# R6DroneElectronics.net
KiCad netlist of a schematic drawn in EAGLE
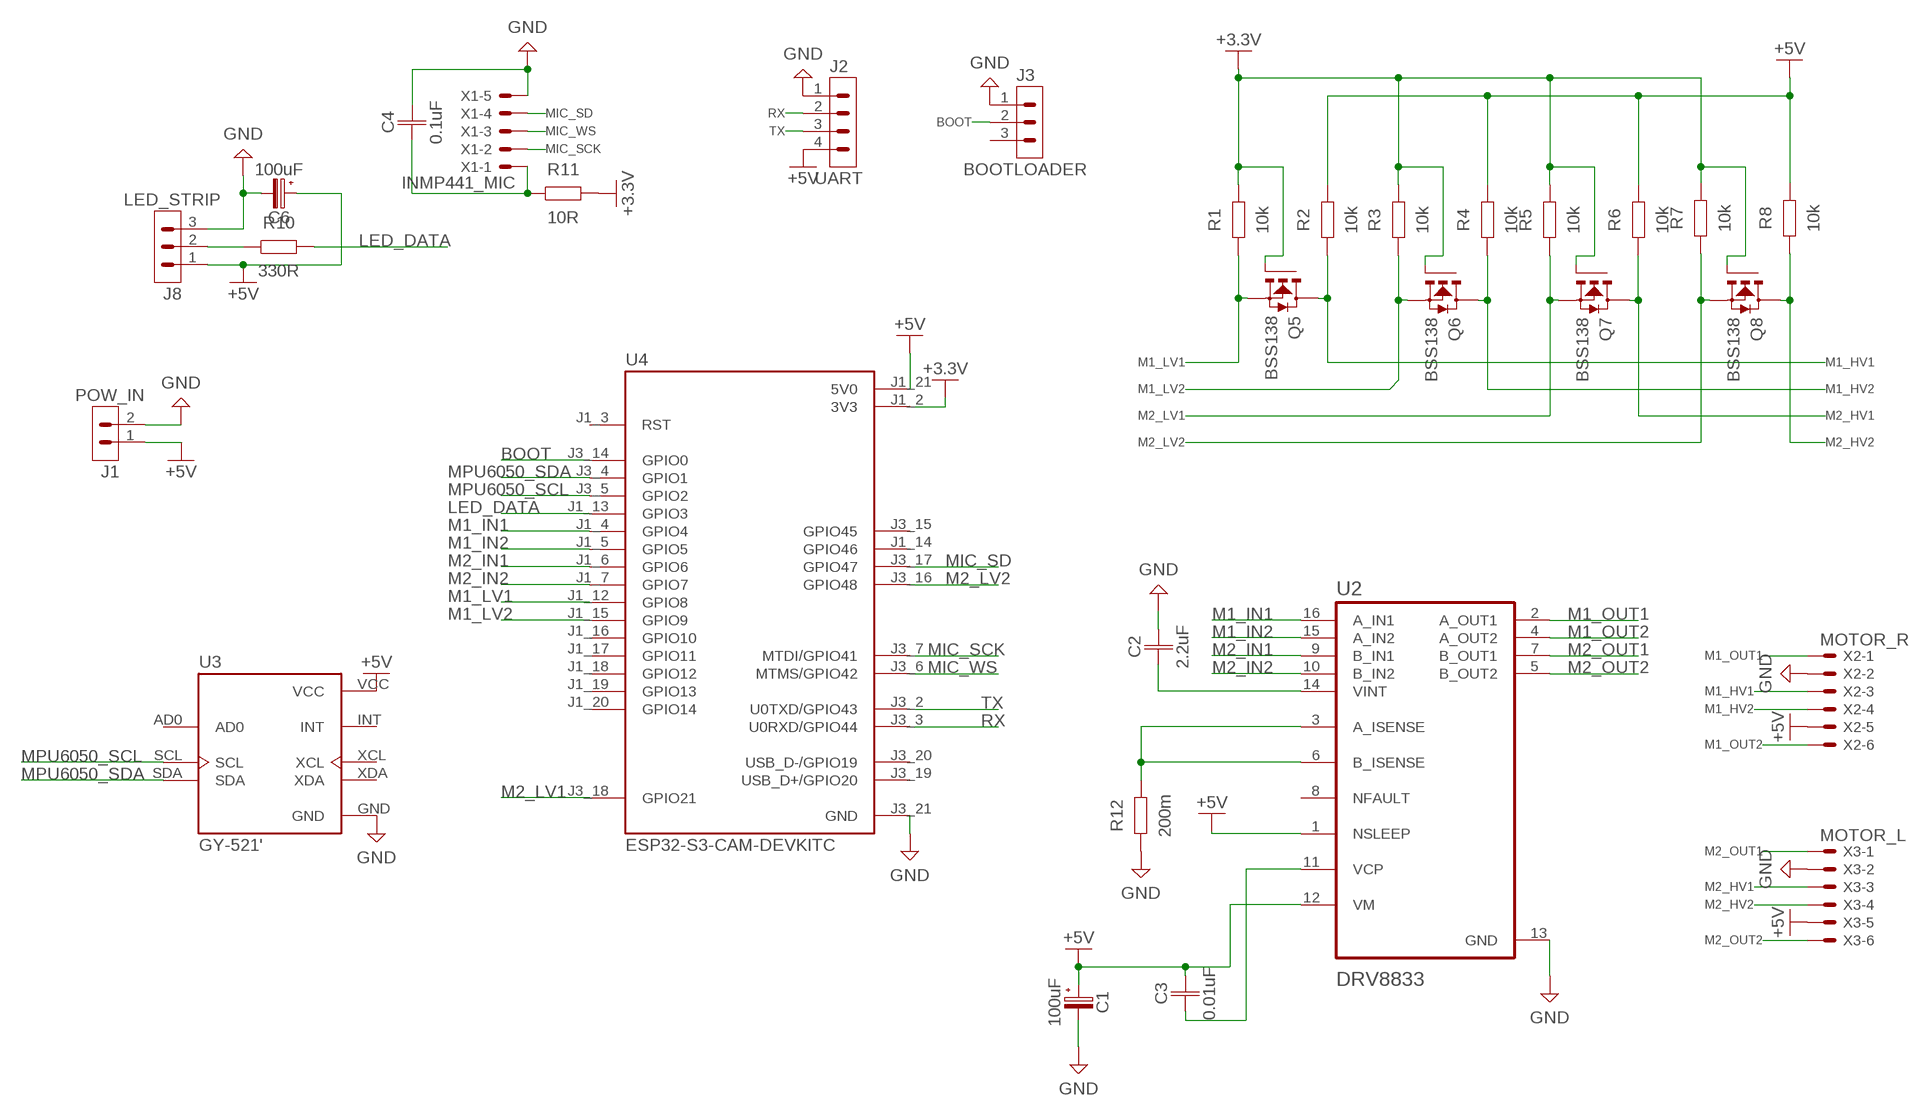
[diagram p0: schematic, sheet 1]

(export (version "E")
  (design (tool "Eeschema 10.0.6"))
  (components
    (comp (ref "C1")
      (value "100uF")
      (footprint "eagle-import:CAPAE1030X1050N")
      (libsource (lib "eagle-import") (part "C-POLECAP-10.5MM_"))
    )
    (comp (ref "C2")
      (value "2.2uF")
      (footprint "eagle-import:CAPC4532X135")
      (libsource (lib "eagle-import") (part "CCHIP-1812(4532-METRIC)_"))
    )
    (comp (ref "C3")
      (value "0.01uF")
      (footprint "eagle-import:CAPC4532X135")
      (libsource (lib "eagle-import") (part "CCHIP-1812(4532-METRIC)_"))
    )
    (comp (ref "C4")
      (value "0.1uF")
      (footprint "eagle-import:CAPC4532X135")
      (libsource (lib "eagle-import") (part "CCHIP-1812(4532-METRIC)_"))
    )
    (comp (ref "C6")
      (value "100uF")
      (footprint "eagle-import:CAPAE1030X1050N")
      (libsource (lib "eagle-import") (part "C-POLECAP-10.5MM_"))
    )
    (comp (ref "J1")
      (value "POW_IN")
      (footprint "eagle-import:B2B-XH-A")
      (fields (field (name "MANUFACTURER") "JST Sales America Inc.") (field (name "MPN") "B2B-XH-A"))
      (libsource (lib "eagle-import") (part "B2B-XH-A"))
    )
    (comp (ref "J2")
      (value "UART")
      (footprint "eagle-import:B4B-XH-A")
      (fields (field (name "MANUFACTURER") "JST Sales America Inc.") (field (name "MPN") "B4B-XH-A"))
      (libsource (lib "eagle-import") (part "B4B-XH-A"))
    )
    (comp (ref "J3")
      (value "BOOTLOADER")
      (footprint "eagle-import:B3B-XH-A")
      (fields (field (name "MANUFACTURER") "JST Sales America Inc.") (field (name "MPN") "B3B-XH-A"))
      (libsource (lib "eagle-import") (part "B3B-XH-A"))
    )
    (comp (ref "J8")
      (value "LED_STRIP")
      (footprint "eagle-import:B3B-XH-A")
      (fields (field (name "MANUFACTURER") "JST Sales America Inc.") (field (name "MPN") "B3B-XH-A"))
      (libsource (lib "eagle-import") (part "B3B-XH-A"))
    )
    (comp (ref "Q5")
      (value "BSS138")
      (footprint "eagle-import:SOT23")
      (fields (field (name "MANUFACTURER") "onsemi") (field (name "MPN") "BSS123L"))
      (libsource (lib "eagle-import") (part "NMOSFET__SOT23-GSDBSS123"))
    )
    (comp (ref "Q6")
      (value "BSS138")
      (footprint "eagle-import:SOT23")
      (fields (field (name "MANUFACTURER") "onsemi") (field (name "MPN") "BSS123L"))
      (libsource (lib "eagle-import") (part "NMOSFET__SOT23-GSDBSS123"))
    )
    (comp (ref "Q7")
      (value "BSS138")
      (footprint "eagle-import:SOT23")
      (fields (field (name "MANUFACTURER") "onsemi") (field (name "MPN") "BSS123L"))
      (libsource (lib "eagle-import") (part "NMOSFET__SOT23-GSDBSS123"))
    )
    (comp (ref "Q8")
      (value "BSS138")
      (footprint "eagle-import:SOT23")
      (fields (field (name "MANUFACTURER") "onsemi") (field (name "MPN") "BSS123L"))
      (libsource (lib "eagle-import") (part "NMOSFET__SOT23-GSDBSS123"))
    )
    (comp (ref "R1")
      (value "10k")
      (footprint "eagle-import:RESC3224X71")
      (libsource (lib "eagle-import") (part "RCHIP-1210(3225-METRIC)_"))
    )
    (comp (ref "R2")
      (value "10k")
      (footprint "eagle-import:RESC3224X71")
      (libsource (lib "eagle-import") (part "RCHIP-1210(3225-METRIC)_"))
    )
    (comp (ref "R3")
      (value "10k")
      (footprint "eagle-import:RESC3224X71")
      (libsource (lib "eagle-import") (part "RCHIP-1210(3225-METRIC)_"))
    )
    (comp (ref "R4")
      (value "10k")
      (footprint "eagle-import:RESC3224X71")
      (libsource (lib "eagle-import") (part "RCHIP-1210(3225-METRIC)_"))
    )
    (comp (ref "R5")
      (value "10k")
      (footprint "eagle-import:RESC3224X71")
      (libsource (lib "eagle-import") (part "RCHIP-1210(3225-METRIC)_"))
    )
    (comp (ref "R6")
      (value "10k")
      (footprint "eagle-import:RESC3224X71")
      (libsource (lib "eagle-import") (part "RCHIP-1210(3225-METRIC)_"))
    )
    (comp (ref "R7")
      (value "10k")
      (footprint "eagle-import:RESC3224X71")
      (libsource (lib "eagle-import") (part "RCHIP-1210(3225-METRIC)_"))
    )
    (comp (ref "R8")
      (value "10k")
      (footprint "eagle-import:RESC3224X71")
      (libsource (lib "eagle-import") (part "RCHIP-1210(3225-METRIC)_"))
    )
    (comp (ref "R10")
      (value "330R")
      (footprint "eagle-import:RESC3224X71")
      (libsource (lib "eagle-import") (part "RCHIP-1210(3225-METRIC)_"))
    )
    (comp (ref "R11")
      (value "10R")
      (footprint "eagle-import:RESC3224X71")
      (libsource (lib "eagle-import") (part "RCHIP-1210(3225-METRIC)_"))
    )
    (comp (ref "R12")
      (value "200m")
      (footprint "eagle-import:RESC3224X71")
      (libsource (lib "eagle-import") (part "RCHIP-1210(3225-METRIC)_"))
    )
    (comp (ref "U2")
      (value "DRV8833")
      (footprint "eagle-import:SOP65P640X120-16N")
      (fields
        (field (name "DIGIKEY_PART_NUMBER") "DRV8833PW-ND")
        (field (name "MF") "Texas Instruments")
        (field (name "MP") "DRV8833PW")
      )
      (libsource (lib "eagle-import") (part "DRV8833PW"))
    )
    (comp (ref "U3")
      (value "GY-521'")
      (footprint "eagle-import:MODULE_GY-521")
      (fields (field (name "MF") "GODREAM FORDREAM CO., LIMITED") (field (name "MP") "GY-521"))
      (libsource (lib "eagle-import") (part "GY-521'"))
    )
    (comp (ref "U4")
      (value "ESP32-S3-CAM-DEVKITC")
      (footprint "eagle-import:ESP32-S3-CAM-DEVKITC")
      (fields (field (name "MF") "Espressif Systems") (field (name "MP") "ESP32-S3-DEVKITC-1-N8R2"))
      (libsource (lib "eagle-import") (part "ESP32-S3-CAM-DEVKITC"))
    )
    (comp (ref "X1")
      (value "INMP441_MIC")
      (footprint "eagle-import:JST-XH-05-PACKAGE-LONG-PAD")
      (libsource (lib "eagle-import") (part "JST-XH-05-PIN-LONG-PAD"))
    )
    (comp (ref "X2")
      (value "MOTOR_R")
      (footprint "eagle-import:JST-XH-06-PACKAGE-LONG-PAD")
      (libsource (lib "eagle-import") (part "JST-XH-06-PIN-LONG-PAD"))
    )
    (comp (ref "X3")
      (value "MOTOR_L")
      (footprint "eagle-import:JST-XH-06-PACKAGE-LONG-PAD")
      (libsource (lib "eagle-import") (part "JST-XH-06-PIN-LONG-PAD"))
    )
  )
  (nets
    (net (code "1") (name "+3.3V") (class "Default")
      (node (ref "Q5") (pin "1") (pinfunction "G_1") (pintype "passive"))
      (node (ref "Q6") (pin "1") (pinfunction "G_1") (pintype "passive"))
      (node (ref "Q7") (pin "1") (pinfunction "G_1") (pintype "passive"))
      (node (ref "Q8") (pin "1") (pinfunction "G_1") (pintype "passive"))
      (node (ref "R1") (pin "2") (pinfunction "2_2") (pintype "passive"))
      (node (ref "R11") (pin "2") (pinfunction "2_2") (pintype "passive"))
      (node (ref "R3") (pin "2") (pinfunction "2_2") (pintype "passive"))
      (node (ref "R5") (pin "2") (pinfunction "2_2") (pintype "passive"))
      (node (ref "R7") (pin "2") (pinfunction "2_2") (pintype "passive"))
      (node (ref "U4") (pin "J1_2") (pinfunction "3V3_J1_2") (pintype "power_in"))
    )
    (net (code "2") (name "+5V") (class "Default")
      (node (ref "C1") (pin "1") (pinfunction "+_1") (pintype "passive"))
      (node (ref "C3") (pin "2") (pinfunction "2_2") (pintype "passive"))
      (node (ref "C6") (pin "1") (pinfunction "+_1") (pintype "passive"))
      (node (ref "J1") (pin "1") (pinfunction "1_1") (pintype "passive"))
      (node (ref "J2") (pin "4") (pinfunction "4_4") (pintype "passive"))
      (node (ref "J8") (pin "1") (pinfunction "1_1") (pintype "passive"))
      (node (ref "R2") (pin "2") (pinfunction "2_2") (pintype "passive"))
      (node (ref "R4") (pin "2") (pinfunction "2_2") (pintype "passive"))
      (node (ref "R6") (pin "2") (pinfunction "2_2") (pintype "passive"))
      (node (ref "R8") (pin "2") (pinfunction "2_2") (pintype "passive"))
      (node (ref "U2") (pin "1") (pinfunction "NSLEEP_1") (pintype "bidirectional"))
      (node (ref "U2") (pin "12") (pinfunction "VM_12") (pintype "bidirectional"))
      (node (ref "U3") (pin "VCC") (pinfunction "VCC_VCC") (pintype "power_in"))
      (node (ref "U4") (pin "J1_21") (pinfunction "5V0_J1_21") (pintype "power_in"))
      (node (ref "X2") (pin "5") (pinfunction "S_5") (pintype "passive"))
      (node (ref "X3") (pin "5") (pinfunction "S_5") (pintype "passive"))
    )
    (net (code "3") (name "/BOOT") (class "Default")
      (node (ref "J3") (pin "2") (pinfunction "2_2") (pintype "passive"))
      (node (ref "U4") (pin "J3_14") (pinfunction "GPIO0_J3_14") (pintype "bidirectional"))
    )
    (net (code "4") (name "/LED_DATA") (class "Default")
      (node (ref "R10") (pin "2") (pinfunction "2_2") (pintype "passive"))
      (node (ref "U4") (pin "J1_13") (pinfunction "GPIO3_J1_13") (pintype "bidirectional"))
    )
    (net (code "5") (name "/M1_HV1") (class "Default")
      (node (ref "Q5") (pin "3") (pinfunction "D_3") (pintype "passive"))
      (node (ref "R2") (pin "1") (pinfunction "1_1") (pintype "passive"))
      (node (ref "X2") (pin "3") (pinfunction "S_3") (pintype "passive"))
    )
    (net (code "6") (name "/M1_HV2") (class "Default")
      (node (ref "Q6") (pin "3") (pinfunction "D_3") (pintype "passive"))
      (node (ref "R4") (pin "1") (pinfunction "1_1") (pintype "passive"))
      (node (ref "X2") (pin "4") (pinfunction "S_4") (pintype "passive"))
    )
    (net (code "7") (name "/M1_IN1") (class "Default")
      (node (ref "U2") (pin "16") (pinfunction "A_IN1_16") (pintype "input"))
      (node (ref "U4") (pin "J1_4") (pinfunction "GPIO4_J1_4") (pintype "bidirectional"))
    )
    (net (code "8") (name "/M1_IN2") (class "Default")
      (node (ref "U2") (pin "15") (pinfunction "A_IN2_15") (pintype "input"))
      (node (ref "U4") (pin "J1_5") (pinfunction "GPIO5_J1_5") (pintype "bidirectional"))
    )
    (net (code "9") (name "/M1_LV1") (class "Default")
      (node (ref "Q5") (pin "2") (pinfunction "S_2") (pintype "passive"))
      (node (ref "R1") (pin "1") (pinfunction "1_1") (pintype "passive"))
      (node (ref "U4") (pin "J1_12") (pinfunction "GPIO8_J1_12") (pintype "bidirectional"))
    )
    (net (code "10") (name "/M1_LV2") (class "Default")
      (node (ref "Q6") (pin "2") (pinfunction "S_2") (pintype "passive"))
      (node (ref "R3") (pin "1") (pinfunction "1_1") (pintype "passive"))
      (node (ref "U4") (pin "J1_15") (pinfunction "GPIO9_J1_15") (pintype "bidirectional"))
    )
    (net (code "11") (name "/M1_OUT1") (class "Default")
      (node (ref "U2") (pin "2") (pinfunction "A_OUT1_2") (pintype "output"))
      (node (ref "X2") (pin "1") (pinfunction "S_1") (pintype "passive"))
    )
    (net (code "12") (name "/M1_OUT2") (class "Default")
      (node (ref "U2") (pin "4") (pinfunction "A_OUT2_4") (pintype "output"))
      (node (ref "X2") (pin "6") (pinfunction "S_6") (pintype "passive"))
    )
    (net (code "13") (name "/M2_HV1") (class "Default")
      (node (ref "Q7") (pin "3") (pinfunction "D_3") (pintype "passive"))
      (node (ref "R6") (pin "1") (pinfunction "1_1") (pintype "passive"))
      (node (ref "X3") (pin "3") (pinfunction "S_3") (pintype "passive"))
    )
    (net (code "14") (name "/M2_HV2") (class "Default")
      (node (ref "Q8") (pin "3") (pinfunction "D_3") (pintype "passive"))
      (node (ref "R8") (pin "1") (pinfunction "1_1") (pintype "passive"))
      (node (ref "X3") (pin "4") (pinfunction "S_4") (pintype "passive"))
    )
    (net (code "15") (name "/M2_IN1") (class "Default")
      (node (ref "U2") (pin "9") (pinfunction "B_IN1_9") (pintype "input"))
      (node (ref "U4") (pin "J1_6") (pinfunction "GPIO6_J1_6") (pintype "bidirectional"))
    )
    (net (code "16") (name "/M2_IN2") (class "Default")
      (node (ref "U2") (pin "10") (pinfunction "B_IN2_10") (pintype "input"))
      (node (ref "U4") (pin "J1_7") (pinfunction "GPIO7_J1_7") (pintype "bidirectional"))
    )
    (net (code "17") (name "/M2_LV1") (class "Default")
      (node (ref "Q7") (pin "2") (pinfunction "S_2") (pintype "passive"))
      (node (ref "R5") (pin "1") (pinfunction "1_1") (pintype "passive"))
      (node (ref "U4") (pin "J3_18") (pinfunction "GPIO21_J3_18") (pintype "bidirectional"))
    )
    (net (code "18") (name "/M2_LV2") (class "Default")
      (node (ref "Q8") (pin "2") (pinfunction "S_2") (pintype "passive"))
      (node (ref "R7") (pin "1") (pinfunction "1_1") (pintype "passive"))
      (node (ref "U4") (pin "J3_16") (pinfunction "GPIO48_J3_16") (pintype "bidirectional"))
    )
    (net (code "19") (name "/M2_OUT1") (class "Default")
      (node (ref "U2") (pin "7") (pinfunction "B_OUT1_7") (pintype "output"))
      (node (ref "X3") (pin "1") (pinfunction "S_1") (pintype "passive"))
    )
    (net (code "20") (name "/M2_OUT2") (class "Default")
      (node (ref "U2") (pin "5") (pinfunction "B_OUT2_5") (pintype "output"))
      (node (ref "X3") (pin "6") (pinfunction "S_6") (pintype "passive"))
    )
    (net (code "21") (name "/MIC_SCK") (class "Default")
      (node (ref "U4") (pin "J3_7") (pinfunction "MTDI/GPIO41_J3_7") (pintype "bidirectional"))
      (node (ref "X1") (pin "2") (pinfunction "S_2") (pintype "passive"))
    )
    (net (code "22") (name "/MIC_SD") (class "Default")
      (node (ref "U4") (pin "J3_17") (pinfunction "GPIO47_J3_17") (pintype "bidirectional"))
      (node (ref "X1") (pin "4") (pinfunction "S_4") (pintype "passive"))
    )
    (net (code "23") (name "/MIC_WS") (class "Default")
      (node (ref "U4") (pin "J3_6") (pinfunction "MTMS/GPIO42_J3_6") (pintype "bidirectional"))
      (node (ref "X1") (pin "3") (pinfunction "S_3") (pintype "passive"))
    )
    (net (code "24") (name "/MPU6050_SCL") (class "Default")
      (node (ref "U3") (pin "SCL") (pinfunction "SCL_SCL") (pintype "input"))
      (node (ref "U4") (pin "J3_5") (pinfunction "GPIO2_J3_5") (pintype "bidirectional"))
    )
    (net (code "25") (name "/MPU6050_SDA") (class "Default")
      (node (ref "U3") (pin "SDA") (pinfunction "SDA_SDA") (pintype "bidirectional"))
      (node (ref "U4") (pin "J3_4") (pinfunction "GPIO1_J3_4") (pintype "bidirectional"))
    )
    (net (code "26") (name "/RX") (class "Default")
      (node (ref "J2") (pin "2") (pinfunction "2_2") (pintype "passive"))
      (node (ref "U4") (pin "J3_3") (pinfunction "U0RXD/GPIO44_J3_3") (pintype "bidirectional"))
    )
    (net (code "27") (name "/TX") (class "Default")
      (node (ref "J2") (pin "3") (pinfunction "3_3") (pintype "passive"))
      (node (ref "U4") (pin "J3_2") (pinfunction "U0TXD/GPIO43_J3_2") (pintype "bidirectional"))
    )
    (net (code "28") (name "GND") (class "Default")
      (node (ref "C1") (pin "2") (pinfunction "-_2") (pintype "passive"))
      (node (ref "C2") (pin "2") (pinfunction "2_2") (pintype "passive"))
      (node (ref "C4") (pin "2") (pinfunction "2_2") (pintype "passive"))
      (node (ref "C6") (pin "2") (pinfunction "-_2") (pintype "passive"))
      (node (ref "J1") (pin "2") (pinfunction "2_2") (pintype "passive"))
      (node (ref "J2") (pin "1") (pinfunction "1_1") (pintype "passive"))
      (node (ref "J3") (pin "1") (pinfunction "1_1") (pintype "passive"))
      (node (ref "J8") (pin "3") (pinfunction "3_3") (pintype "passive"))
      (node (ref "R12") (pin "1") (pinfunction "1_1") (pintype "passive"))
      (node (ref "U2") (pin "13") (pinfunction "GND_13") (pintype "power_in"))
      (node (ref "U3") (pin "GND") (pinfunction "GND_GND") (pintype "power_in"))
      (node (ref "U4") (pin "J3_21") (pinfunction "GND_J3_21") (pintype "power_in"))
      (node (ref "X1") (pin "5") (pinfunction "S_5") (pintype "passive"))
      (node (ref "X2") (pin "2") (pinfunction "S_2") (pintype "passive"))
      (node (ref "X3") (pin "2") (pinfunction "S_2") (pintype "passive"))
    )
    (net (code "29") (name "Net-(J8-Pad2)") (class "Default")
      (node (ref "J8") (pin "2") (pinfunction "2_2") (pintype "passive"))
      (node (ref "R10") (pin "1") (pinfunction "1_1") (pintype "passive"))
    )
    (net (code "30") (name "Net-(U2-A_ISENSE)") (class "Default")
      (node (ref "R12") (pin "2") (pinfunction "2_2") (pintype "passive"))
      (node (ref "U2") (pin "3") (pinfunction "A_ISENSE_3") (pintype "bidirectional"))
      (node (ref "U2") (pin "6") (pinfunction "B_ISENSE_6") (pintype "bidirectional"))
    )
    (net (code "31") (name "Net-(U2-VCP)") (class "Default")
      (node (ref "C3") (pin "1") (pinfunction "1_1") (pintype "passive"))
      (node (ref "U2") (pin "11") (pinfunction "VCP_11") (pintype "bidirectional"))
    )
    (net (code "32") (name "Net-(U2-VINT)") (class "Default")
      (node (ref "C2") (pin "1") (pinfunction "1_1") (pintype "passive"))
      (node (ref "U2") (pin "14") (pinfunction "VINT_14") (pintype "input"))
    )
    (net (code "33") (name "Net-(X1A-S)") (class "Default")
      (node (ref "C4") (pin "1") (pinfunction "1_1") (pintype "passive"))
      (node (ref "R11") (pin "1") (pinfunction "1_1") (pintype "passive"))
      (node (ref "X1") (pin "1") (pinfunction "S_1") (pintype "passive"))
    )
    (net (code "34") (name "unconnected-(J3-Pad3)") (class "Default")
      (node (ref "J3") (pin "3") (pinfunction "3_3") (pintype "passive"))
    )
    (net (code "35") (name "unconnected-(U2-NFAULT-Pad8)") (class "Default")
      (node (ref "U2") (pin "8") (pinfunction "NFAULT_8") (pintype "bidirectional"))
    )
    (net (code "36") (name "unconnected-(U3-PadAD0)") (class "Default")
      (node (ref "U3") (pin "AD0") (pinfunction "AD0_AD0") (pintype "input"))
    )
    (net (code "37") (name "unconnected-(U3-PadINT)") (class "Default")
      (node (ref "U3") (pin "INT") (pinfunction "INT_INT") (pintype "output"))
    )
    (net (code "38") (name "unconnected-(U3-PadXCL)") (class "Default")
      (node (ref "U3") (pin "XCL") (pinfunction "XCL_XCL") (pintype "output"))
    )
    (net (code "39") (name "unconnected-(U3-PadXDA)") (class "Default")
      (node (ref "U3") (pin "XDA") (pinfunction "XDA_XDA") (pintype "bidirectional"))
    )
    (net (code "40") (name "unconnected-(U4-GPIO10-PadJ1_16)") (class "Default")
      (node (ref "U4") (pin "J1_16") (pinfunction "GPIO10_J1_16") (pintype "bidirectional"))
    )
    (net (code "41") (name "unconnected-(U4-GPIO11-PadJ1_17)") (class "Default")
      (node (ref "U4") (pin "J1_17") (pinfunction "GPIO11_J1_17") (pintype "bidirectional"))
    )
    (net (code "42") (name "unconnected-(U4-GPIO12-PadJ1_18)") (class "Default")
      (node (ref "U4") (pin "J1_18") (pinfunction "GPIO12_J1_18") (pintype "bidirectional"))
    )
    (net (code "43") (name "unconnected-(U4-GPIO13-PadJ1_19)") (class "Default")
      (node (ref "U4") (pin "J1_19") (pinfunction "GPIO13_J1_19") (pintype "bidirectional"))
    )
    (net (code "44") (name "unconnected-(U4-GPIO14-PadJ1_20)") (class "Default")
      (node (ref "U4") (pin "J1_20") (pinfunction "GPIO14_J1_20") (pintype "bidirectional"))
    )
    (net (code "45") (name "unconnected-(U4-GPIO45-PadJ3_15)") (class "Default")
      (node (ref "U4") (pin "J3_15") (pinfunction "GPIO45_J3_15") (pintype "bidirectional"))
    )
    (net (code "46") (name "unconnected-(U4-GPIO46-PadJ1_14)") (class "Default")
      (node (ref "U4") (pin "J1_14") (pinfunction "GPIO46_J1_14") (pintype "bidirectional"))
    )
    (net (code "47") (name "unconnected-(U4-RST-PadJ1_3)") (class "Default")
      (node (ref "U4") (pin "J1_3") (pinfunction "RST_J1_3") (pintype "input"))
    )
    (net (code "48") (name "unconnected-(U4-USB_D+{slash}GPIO20-PadJ3_19)") (class "Default")
      (node (ref "U4") (pin "J3_19") (pinfunction "USB_D+/GPIO20_J3_19") (pintype "bidirectional"))
    )
    (net (code "49") (name "unconnected-(U4-USB_D-{slash}GPIO19-PadJ3_20)") (class "Default")
      (node (ref "U4") (pin "J3_20") (pinfunction "USB_D-/GPIO19_J3_20") (pintype "bidirectional"))
    )
  )
)
